# fan_controller.net
KiCad netlist of a schematic drawn in EAGLE
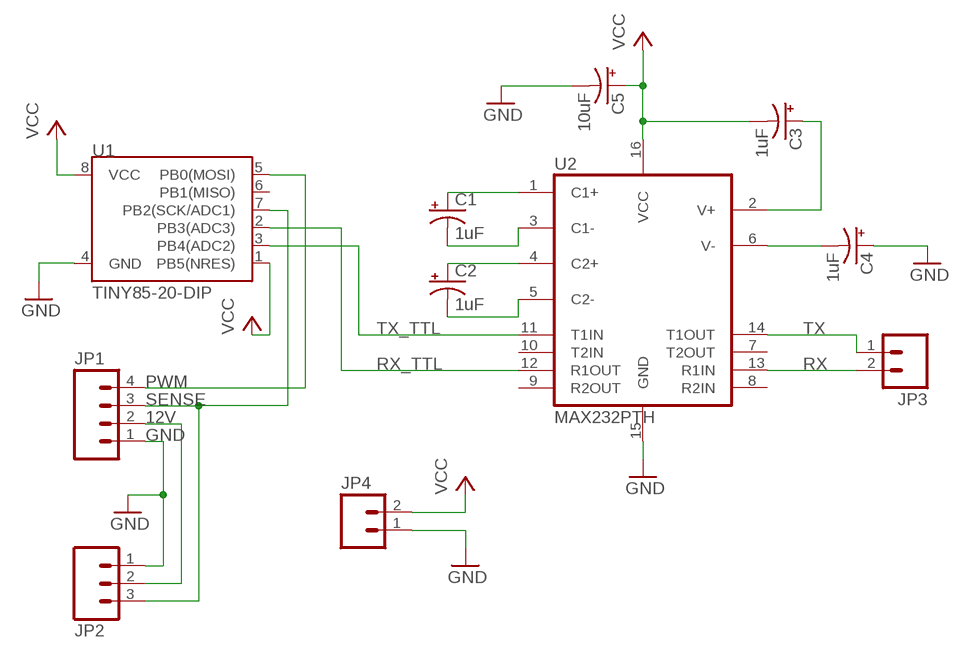
[diagram p0: schematic, sheet 1]

(export (version "E")
  (design (tool "Eeschema 10.0.6"))
  (components
    (comp (ref "C1")
      (value "1uF")
      (footprint "eagle-import:CPOL-RADIAL-10UF-25V")
      (libsource (lib "eagle-import") (part "CAP_POLPTH2"))
    )
    (comp (ref "C2")
      (value "1uF")
      (footprint "eagle-import:CPOL-RADIAL-10UF-25V")
      (libsource (lib "eagle-import") (part "CAP_POLPTH2"))
    )
    (comp (ref "C3")
      (value "1uF")
      (footprint "eagle-import:CPOL-RADIAL-10UF-25V")
      (libsource (lib "eagle-import") (part "CAP_POLPTH2"))
    )
    (comp (ref "C4")
      (value "1uF")
      (footprint "eagle-import:CPOL-RADIAL-10UF-25V")
      (libsource (lib "eagle-import") (part "CAP_POLPTH2"))
    )
    (comp (ref "C5")
      (value "10uF")
      (footprint "eagle-import:CPOL-RADIAL-10UF-25V")
      (libsource (lib "eagle-import") (part "CAP_POLPTH2"))
    )
    (comp (ref "JP1")
      (value "M04PTH")
      (footprint "eagle-import:1X04")
      (libsource (lib "eagle-import") (part "M04PTH"))
    )
    (comp (ref "JP2")
      (value "M03PTH")
      (footprint "eagle-import:1X03")
      (libsource (lib "eagle-import") (part "M03PTH"))
    )
    (comp (ref "JP3")
      (value "M02PTH")
      (footprint "eagle-import:1X02")
      (libsource (lib "eagle-import") (part "M02PTH"))
    )
    (comp (ref "JP4")
      (value "M02PTH")
      (footprint "eagle-import:1X02")
      (libsource (lib "eagle-import") (part "M02PTH"))
    )
    (comp (ref "U1")
      (value "TINY85-20-DIP")
      (footprint "eagle-import:DIP08")
      (libsource (lib "eagle-import") (part "ATTINY45TINY85-20-DIP"))
    )
    (comp (ref "U2")
      (value "MAX232PTH")
      (footprint "eagle-import:DIL16")
      (libsource (lib "eagle-import") (part "MAX232PTH"))
    )
  )
  (nets
    (net (code "1") (name "/12V") (class "Default")
      (node (ref "JP1") (pin "2") (pinfunction "2_2") (pintype "passive"))
      (node (ref "JP2") (pin "2") (pinfunction "2_2") (pintype "passive"))
    )
    (net (code "2") (name "/PWM") (class "Default")
      (node (ref "JP1") (pin "4") (pinfunction "4_4") (pintype "passive"))
      (node (ref "U1") (pin "5") (pinfunction "PB0(MOSI)_5") (pintype "bidirectional"))
    )
    (net (code "3") (name "/RX") (class "Default")
      (node (ref "JP3") (pin "2") (pinfunction "2_2") (pintype "passive"))
      (node (ref "U2") (pin "13") (pinfunction "R1IN_13") (pintype "input"))
    )
    (net (code "4") (name "/RX_TTL") (class "Default")
      (node (ref "U1") (pin "2") (pinfunction "PB3(ADC3)_2") (pintype "bidirectional"))
      (node (ref "U2") (pin "12") (pinfunction "R1OUT_12") (pintype "output"))
    )
    (net (code "5") (name "/SENSE") (class "Default")
      (node (ref "JP1") (pin "3") (pinfunction "3_3") (pintype "passive"))
      (node (ref "JP2") (pin "3") (pinfunction "3_3") (pintype "passive"))
      (node (ref "U1") (pin "7") (pinfunction "PB2(SCK/ADC1)_7") (pintype "bidirectional"))
    )
    (net (code "6") (name "/TX") (class "Default")
      (node (ref "JP3") (pin "1") (pinfunction "1_1") (pintype "passive"))
      (node (ref "U2") (pin "14") (pinfunction "T1OUT_14") (pintype "output"))
    )
    (net (code "7") (name "/TX_TTL") (class "Default")
      (node (ref "U1") (pin "3") (pinfunction "PB4(ADC2)_3") (pintype "bidirectional"))
      (node (ref "U2") (pin "11") (pinfunction "T1IN_11") (pintype "input"))
    )
    (net (code "8") (name "GND") (class "Default")
      (node (ref "C4") (pin "1") (pinfunction "+_1") (pintype "passive"))
      (node (ref "C5") (pin "2") (pinfunction "-_2") (pintype "passive"))
      (node (ref "JP1") (pin "1") (pinfunction "1_1") (pintype "passive"))
      (node (ref "JP2") (pin "1") (pinfunction "1_1") (pintype "passive"))
      (node (ref "JP4") (pin "1") (pinfunction "1_1") (pintype "passive"))
      (node (ref "U1") (pin "4") (pinfunction "GND_4") (pintype "bidirectional"))
      (node (ref "U2") (pin "15") (pinfunction "GND_15") (pintype "bidirectional"))
    )
    (net (code "9") (name "Net-(C1-+)") (class "Default")
      (node (ref "C1") (pin "1") (pinfunction "+_1") (pintype "passive"))
      (node (ref "U2") (pin "1") (pinfunction "C1+_1") (pintype "bidirectional"))
    )
    (net (code "10") (name "Net-(C1--)") (class "Default")
      (node (ref "C1") (pin "2") (pinfunction "-_2") (pintype "passive"))
      (node (ref "U2") (pin "3") (pinfunction "C1-_3") (pintype "bidirectional"))
    )
    (net (code "11") (name "Net-(C2-+)") (class "Default")
      (node (ref "C2") (pin "1") (pinfunction "+_1") (pintype "passive"))
      (node (ref "U2") (pin "4") (pinfunction "C2+_4") (pintype "bidirectional"))
    )
    (net (code "12") (name "Net-(C2--)") (class "Default")
      (node (ref "C2") (pin "2") (pinfunction "-_2") (pintype "passive"))
      (node (ref "U2") (pin "5") (pinfunction "C2-_5") (pintype "bidirectional"))
    )
    (net (code "13") (name "Net-(C3-+)") (class "Default")
      (node (ref "C3") (pin "1") (pinfunction "+_1") (pintype "passive"))
      (node (ref "U2") (pin "2") (pinfunction "V+_2") (pintype "bidirectional"))
    )
    (net (code "14") (name "Net-(C4--)") (class "Default")
      (node (ref "C4") (pin "2") (pinfunction "-_2") (pintype "passive"))
      (node (ref "U2") (pin "6") (pinfunction "V-_6") (pintype "bidirectional"))
    )
    (net (code "15") (name "VCC") (class "Default")
      (node (ref "C3") (pin "2") (pinfunction "-_2") (pintype "passive"))
      (node (ref "C5") (pin "1") (pinfunction "+_1") (pintype "passive"))
      (node (ref "JP4") (pin "2") (pinfunction "2_2") (pintype "passive"))
      (node (ref "U1") (pin "1") (pinfunction "PB5(NRES)_1") (pintype "bidirectional"))
      (node (ref "U1") (pin "8") (pinfunction "VCC_8") (pintype "bidirectional"))
      (node (ref "U2") (pin "16") (pinfunction "VCC_16") (pintype "bidirectional"))
    )
    (net (code "16") (name "unconnected-(U1-PB1(MISO)-Pad6)") (class "Default")
      (node (ref "U1") (pin "6") (pinfunction "PB1(MISO)_6") (pintype "bidirectional"))
    )
    (net (code "17") (name "unconnected-(U2-R2IN-Pad8)") (class "Default")
      (node (ref "U2") (pin "8") (pinfunction "R2IN_8") (pintype "input"))
    )
    (net (code "18") (name "unconnected-(U2-R2OUT-Pad9)") (class "Default")
      (node (ref "U2") (pin "9") (pinfunction "R2OUT_9") (pintype "output"))
    )
    (net (code "19") (name "unconnected-(U2-T2IN-Pad10)") (class "Default")
      (node (ref "U2") (pin "10") (pinfunction "T2IN_10") (pintype "input"))
    )
    (net (code "20") (name "unconnected-(U2-T2OUT-Pad7)") (class "Default")
      (node (ref "U2") (pin "7") (pinfunction "T2OUT_7") (pintype "output"))
    )
  )
)
